# PJ23.net
KiCad netlist of a schematic drawn in EAGLE
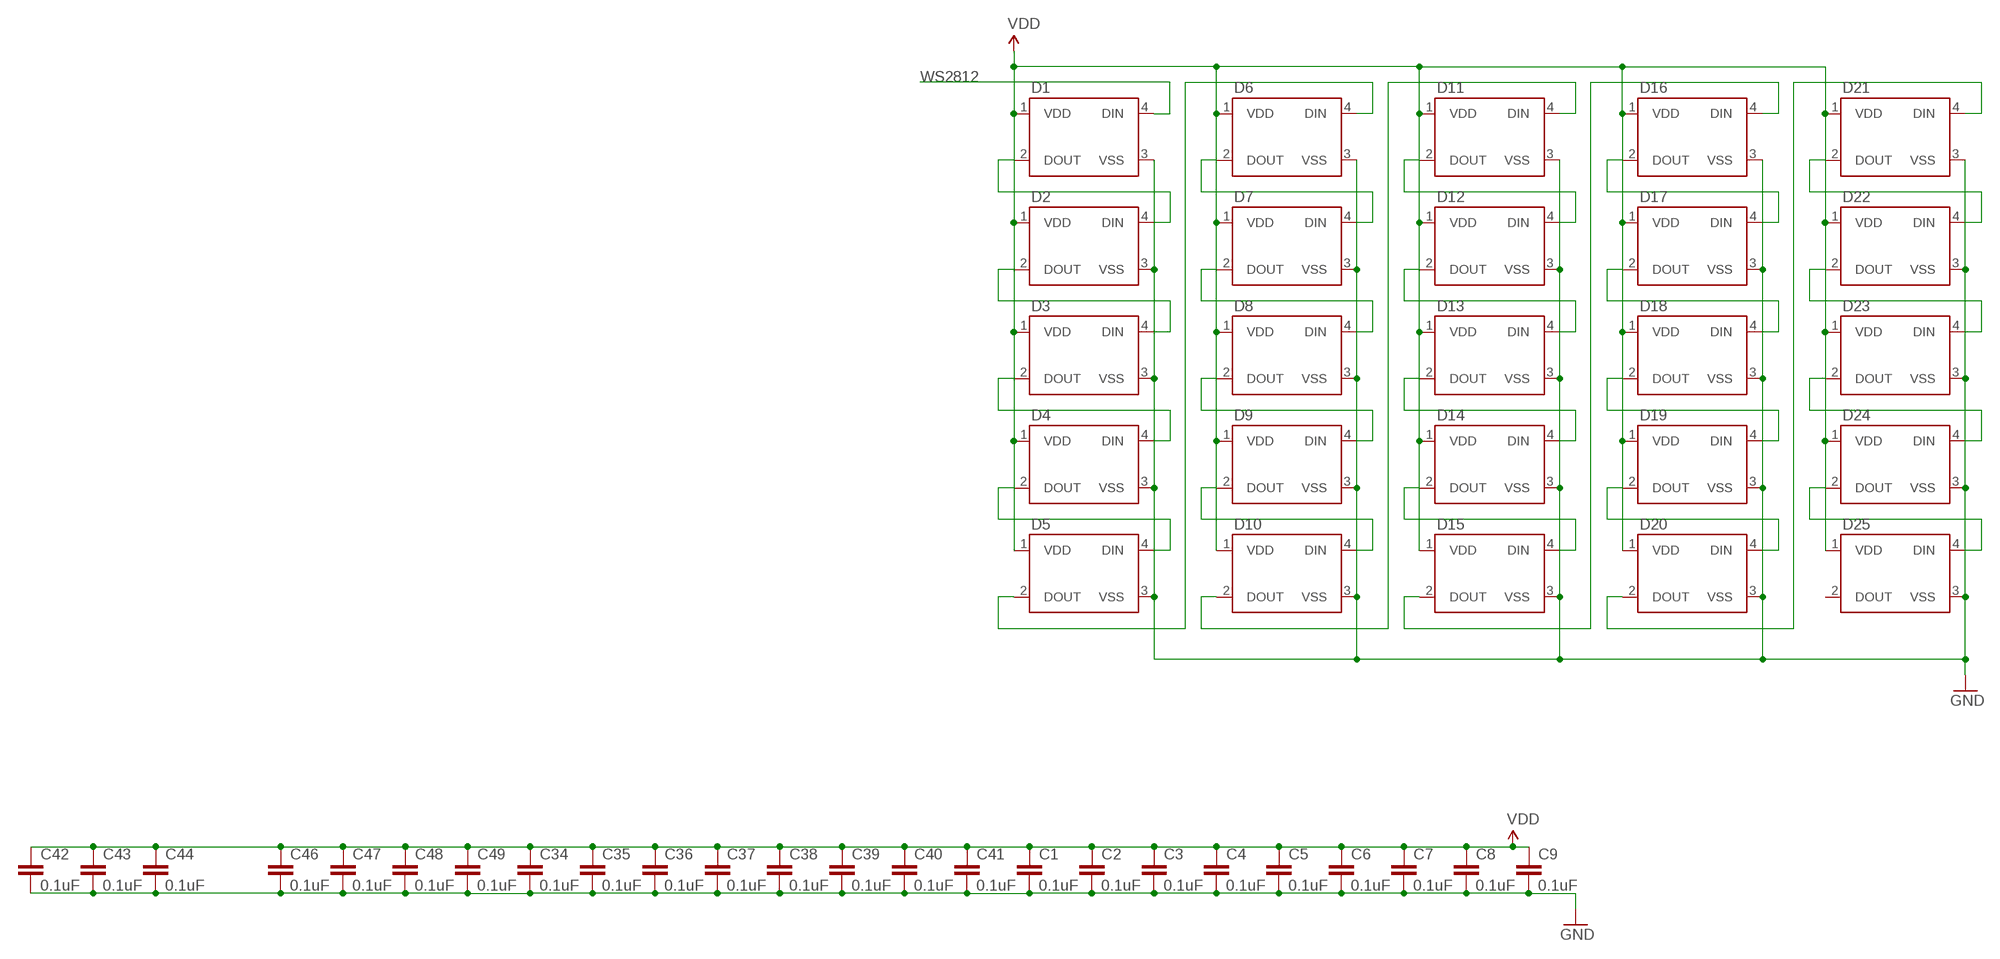
[diagram p0: schematic, sheet 1]
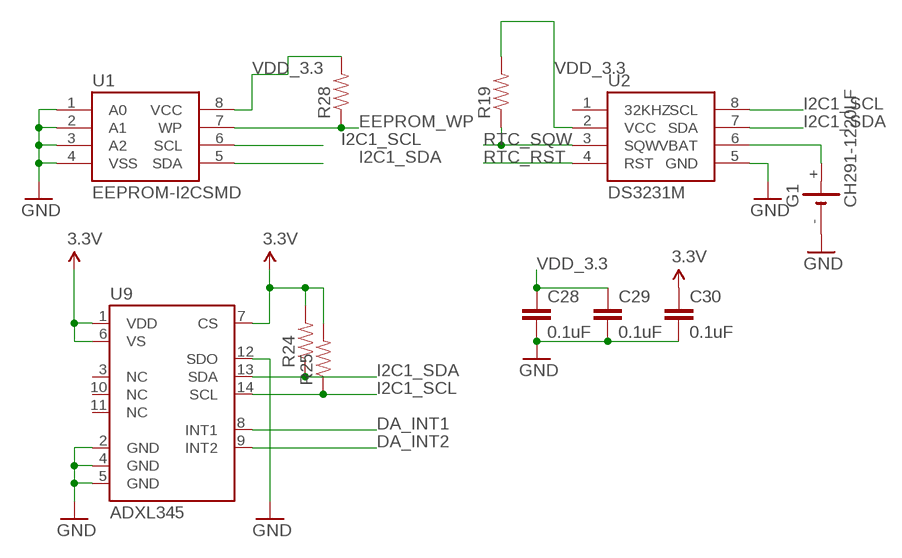
[diagram p1: schematic, sheet 2]
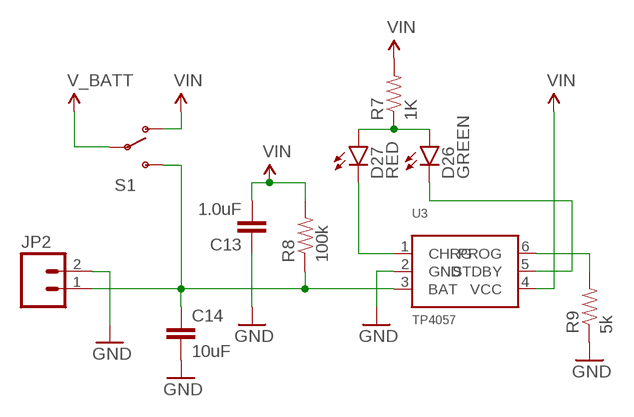
[diagram p2: schematic, sheet 3]
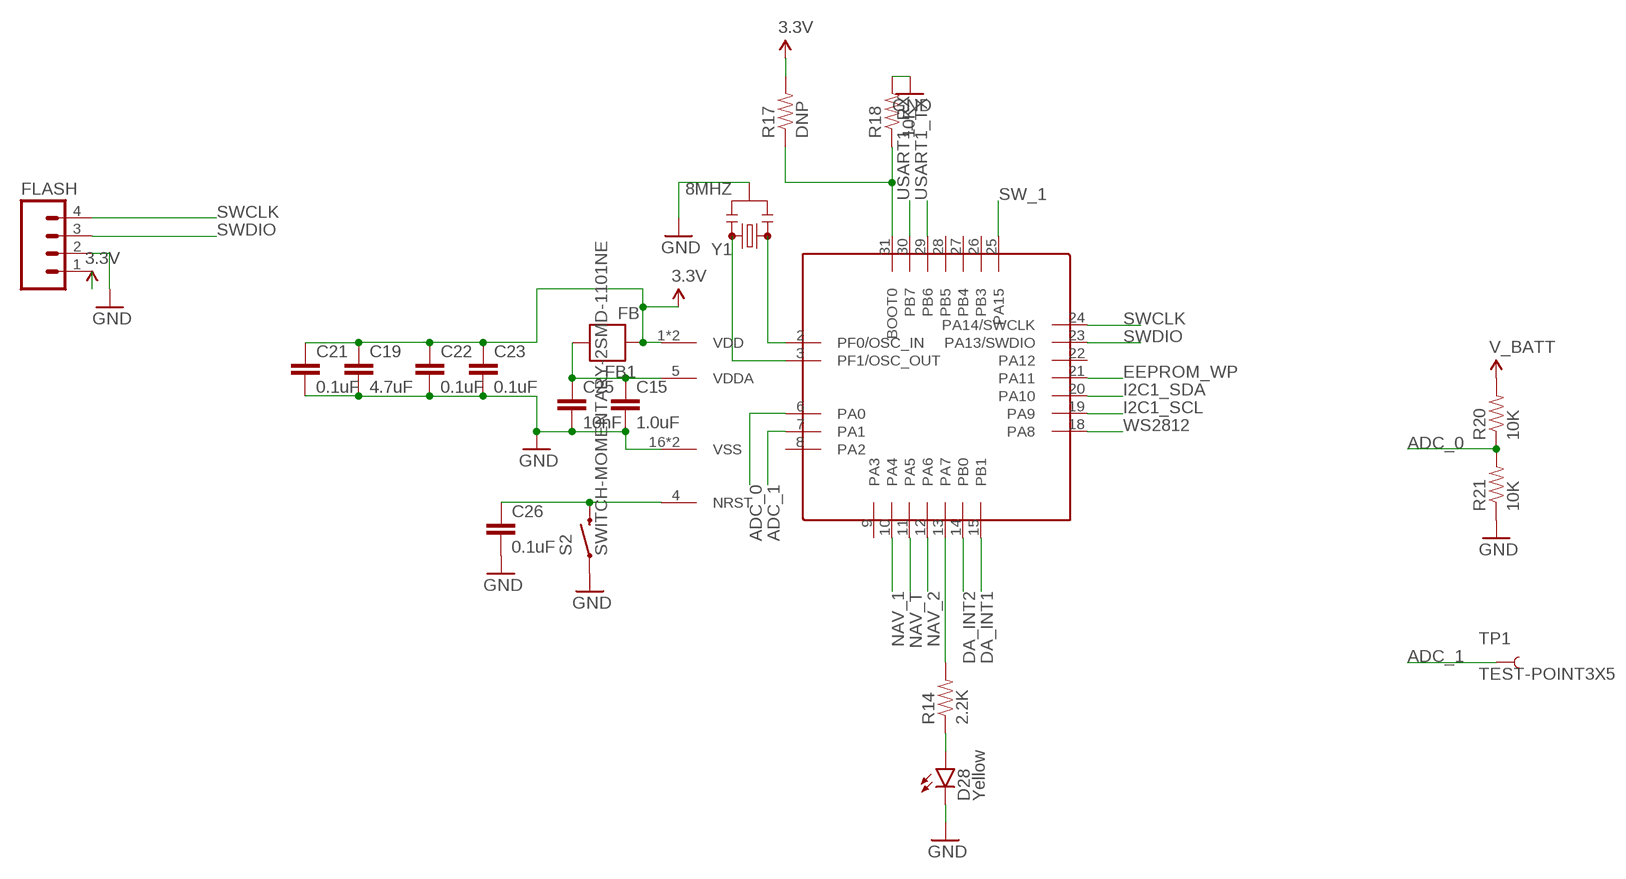
[diagram p3: schematic, sheet 4]
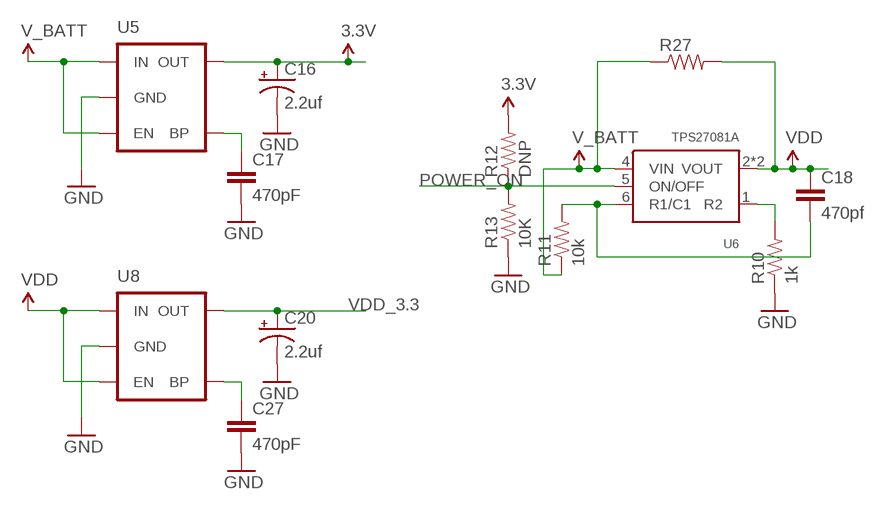
[diagram p4: schematic, sheet 5]
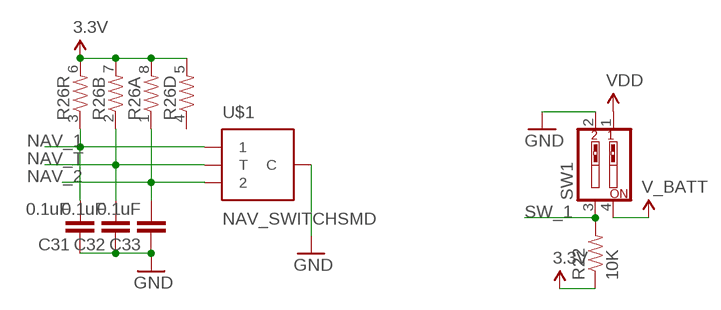
[diagram p5: schematic, sheet 6]
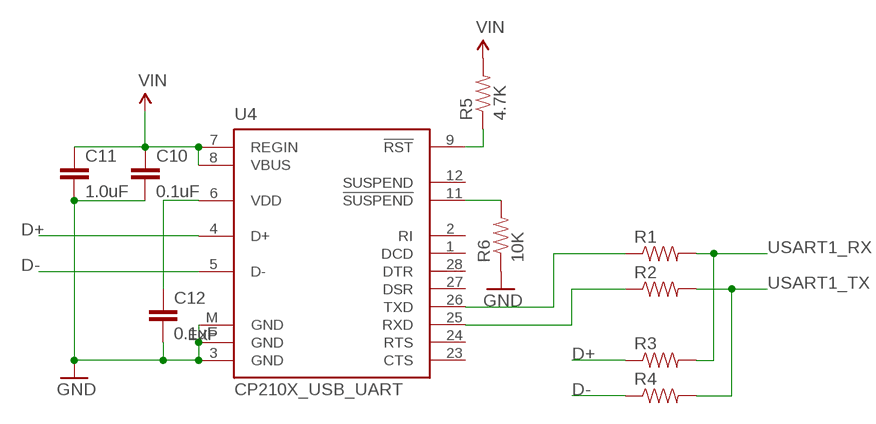
[diagram p6: schematic, sheet 7]
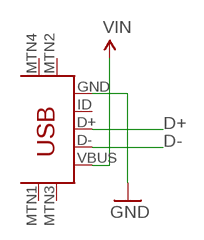
[diagram p7: schematic, sheet 8]

(export (version "E")
  (design (tool "Eeschema 10.0.6"))
  (components
    (comp (ref "JP1")
      (value "USB-MINIB-5PIN")
      (footprint "eagle-import:USB-MINIB")
      (libsource (lib "eagle-import") (part "USB-MINIB-5PIN"))
    )
    (comp (ref "C13")
      (value "1.0uF")
      (footprint "eagle-import:0805-CAP")
      (libsource (lib "eagle-import") (part "1.0UF-25V-+80/-20(0805){dblquote}"))
    )
    (comp (ref "C14")
      (value "10uF")
      (footprint "eagle-import:1206")
      (libsource (lib "eagle-import") (part "10UF-6.3V-20%(1206)"))
    )
    (comp (ref "D26")
      (value "GREEN")
      (footprint "eagle-import:LED-0603")
      (libsource (lib "eagle-import") (part "LED-GREEN0603"))
    )
    (comp (ref "D27")
      (value "RED")
      (footprint "eagle-import:LED-0603")
      (libsource (lib "eagle-import") (part "LED-RED0603"))
    )
    (comp (ref "JP2")
      (value "M02LOCK")
      (footprint "eagle-import:1X02_LOCK")
      (libsource (lib "eagle-import") (part "M02LOCK"))
    )
    (comp (ref "R7")
      (value "1K")
      (footprint "eagle-import:0603-RES")
      (libsource (lib "eagle-import") (part "1KOHM-1/10W-1%(0603)"))
    )
    (comp (ref "R8")
      (value "100k")
      (footprint "eagle-import:0603-RES")
      (libsource (lib "eagle-import") (part "100KOHM-1/10W-1%(0603)"))
    )
    (comp (ref "R9")
      (value "5k")
      (footprint "eagle-import:0805")
      (libsource (lib "eagle-import") (part "RESISTOR0805-RES"))
    )
    (comp (ref "S1")
      (value "SWITCH-SPDT-SMD-A")
      (footprint "eagle-import:SWITCH-SPST-SMD-A")
      (libsource (lib "eagle-import") (part "SWITCH-SPDT-SMD-A"))
    )
    (comp (ref "U3")
      (value "TP4057")
      (footprint "eagle-import:SOT23-6")
      (libsource (lib "eagle-import") (part "TP4057"))
    )
    (comp (ref "C10")
      (value "0.1uF")
      (footprint "eagle-import:0603-CAP")
      (libsource (lib "eagle-import") (part "0.1UF-25V-5%(0603)"))
    )
    (comp (ref "C11")
      (value "1.0uF")
      (footprint "eagle-import:0805-CAP")
      (libsource (lib "eagle-import") (part "1.0UF-25V-+80/-20(0805){dblquote}"))
    )
    (comp (ref "C12")
      (value "0.1uF")
      (footprint "eagle-import:0603-CAP")
      (libsource (lib "eagle-import") (part "0.1UF-25V-5%(0603)"))
    )
    (comp (ref "R1")
      (value "RESISTOR0603")
      (footprint "eagle-import:0603-RES")
      (libsource (lib "eagle-import") (part "RESISTOR0603"))
    )
    (comp (ref "R2")
      (value "RESISTOR0603")
      (footprint "eagle-import:0603-RES")
      (libsource (lib "eagle-import") (part "RESISTOR0603"))
    )
    (comp (ref "R3")
      (value "RESISTOR0603")
      (footprint "eagle-import:0603-RES")
      (libsource (lib "eagle-import") (part "RESISTOR0603"))
    )
    (comp (ref "R4")
      (value "RESISTOR0603")
      (footprint "eagle-import:0603-RES")
      (libsource (lib "eagle-import") (part "RESISTOR0603"))
    )
    (comp (ref "R5")
      (value "4.7K")
      (footprint "eagle-import:0603-RES")
      (libsource (lib "eagle-import") (part "4.7KOHM-1/10W-1%(0603)"))
    )
    (comp (ref "R6")
      (value "10K")
      (footprint "eagle-import:0603-RES")
      (libsource (lib "eagle-import") (part "10KOHM-1/10W-1%(0603)0603"))
    )
    (comp (ref "U4")
      (value "CP210X_USB_UART")
      (footprint "eagle-import:MLP28")
      (libsource (lib "eagle-import") (part "CP210X_USB_UART"))
    )
    (comp (ref "C15")
      (value "1.0uF")
      (footprint "eagle-import:0603-CAP")
      (libsource (lib "eagle-import") (part "1.0UF-16V-10%(0603)"))
    )
    (comp (ref "C19")
      (value "4.7uF")
      (footprint "eagle-import:0603-CAP")
      (libsource (lib "eagle-import") (part "4.7UF-6.3V-10%(0603)0603"))
    )
    (comp (ref "C21")
      (value "0.1uF")
      (footprint "eagle-import:0402-CAP")
      (libsource (lib "eagle-import") (part "CAP0402-CAP"))
    )
    (comp (ref "C22")
      (value "0.1uF")
      (footprint "eagle-import:0402-CAP")
      (libsource (lib "eagle-import") (part "CAP0402-CAP"))
    )
    (comp (ref "C23")
      (value "0.1uF")
      (footprint "eagle-import:0402-CAP")
      (libsource (lib "eagle-import") (part "CAP0402-CAP"))
    )
    (comp (ref "C25")
      (value "10nF")
      (footprint "eagle-import:0402-CAP")
      (libsource (lib "eagle-import") (part "CAP0402-CAP"))
    )
    (comp (ref "C26")
      (value "0.1uF")
      (footprint "eagle-import:0402-CAP")
      (libsource (lib "eagle-import") (part "CAP0402-CAP"))
    )
    (comp (ref "D28")
      (value "Yellow")
      (footprint "eagle-import:LED-0603")
      (libsource (lib "eagle-import") (part "LED-YELLOW0603"))
    )
    (comp (ref "FB1")
      (value "FB")
      (footprint "eagle-import:0603")
      (libsource (lib "eagle-import") (part "FB"))
    )
    (comp (ref "FLASH")
      (value "M04SMD")
      (footprint "eagle-import:1X04-SMD")
      (libsource (lib "eagle-import") (part "M04SMD"))
    )
    (comp (ref "R14")
      (value "2.2K")
      (footprint "eagle-import:0402-RES")
      (libsource (lib "eagle-import") (part "RESISTOR0402"))
    )
    (comp (ref "R17")
      (value "DNP")
      (footprint "eagle-import:0402-RES")
      (libsource (lib "eagle-import") (part "22OHM1/10W1%(0402)"))
    )
    (comp (ref "R18")
      (value "10K")
      (footprint "eagle-import:0402-RES")
      (libsource (lib "eagle-import") (part "22OHM1/10W1%(0402)"))
    )
    (comp (ref "R20")
      (value "10K")
      (footprint "eagle-import:0402-RES")
      (libsource (lib "eagle-import") (part "22OHM1/10W1%(0402)"))
    )
    (comp (ref "R21")
      (value "10K")
      (footprint "eagle-import:0402-RES")
      (libsource (lib "eagle-import") (part "22OHM1/10W1%(0402)"))
    )
    (comp (ref "S2")
      (value "SWITCH-MOMENTARY-2SMD-1101NE")
      (footprint "eagle-import:TACTILE-SWITCH-1101NE")
      (libsource (lib "eagle-import") (part "SWITCH-MOMENTARY-2SMD-1101NE"))
    )
    (comp (ref "TP1")
      (value "TEST-POINT3X5")
      (footprint "eagle-import:PAD.03X.05")
      (libsource (lib "eagle-import") (part "TEST-POINT3X5"))
    )
    (comp (ref "U7")
      (value "STM32F030K6P6")
      (footprint "eagle-import:LQFP32-0.8")
      (libsource (lib "eagle-import") (part "STM32F030K6P6"))
    )
    (comp (ref "Y1")
      (value "8MHZ")
      (footprint "eagle-import:RESONATOR-SMD")
      (libsource (lib "eagle-import") (part "RESONATOR8MHZ"))
    )
    (comp (ref "C16")
      (value "2.2uf")
      (footprint "eagle-import:EIA3216")
      (libsource (lib "eagle-import") (part "10UF-16V-10%(TANT)"))
    )
    (comp (ref "C17")
      (value "470pF")
      (footprint "eagle-import:0805")
      (libsource (lib "eagle-import") (part "SparkFun-Passives_CAP0805"))
    )
    (comp (ref "C18")
      (value "470pf")
      (footprint "eagle-import:1206")
      (libsource (lib "eagle-import") (part "CAP1206"))
    )
    (comp (ref "C20")
      (value "2.2uf")
      (footprint "eagle-import:EIA3216")
      (libsource (lib "eagle-import") (part "10UF-16V-10%(TANT)"))
    )
    (comp (ref "C27")
      (value "470pF")
      (footprint "eagle-import:0805")
      (libsource (lib "eagle-import") (part "SparkFun-Passives_CAP0805"))
    )
    (comp (ref "R10")
      (value "1k")
      (footprint "eagle-import:0805")
      (libsource (lib "eagle-import") (part "RESISTOR0805-RES"))
    )
    (comp (ref "R11")
      (value "10k")
      (footprint "eagle-import:0805")
      (libsource (lib "eagle-import") (part "RESISTOR0805-RES"))
    )
    (comp (ref "R12")
      (value "DNP")
      (footprint "eagle-import:0603-RES")
      (libsource (lib "eagle-import") (part "10KOHM-1/10W-1%(0603)0603"))
    )
    (comp (ref "R13")
      (value "10K")
      (footprint "eagle-import:0603-RES")
      (libsource (lib "eagle-import") (part "10KOHM-1/10W-1%(0603)0603"))
    )
    (comp (ref "R27")
      (value "RESISTOR0805-RES")
      (footprint "eagle-import:0805")
      (libsource (lib "eagle-import") (part "RESISTOR0805-RES"))
    )
    (comp (ref "U5")
      (value "MIC52053.3V")
      (footprint "eagle-import:SOT23-5")
      (libsource (lib "eagle-import") (part "MIC52053.3V"))
    )
    (comp (ref "U6")
      (value "TPS27081A")
      (footprint "eagle-import:DDC(R-PDSO-G6)")
      (libsource (lib "eagle-import") (part "TPS27081A"))
    )
    (comp (ref "U8")
      (value "MIC52053.3V")
      (footprint "eagle-import:SOT23-5")
      (libsource (lib "eagle-import") (part "MIC52053.3V"))
    )
    (comp (ref "C31")
      (value "0.1uF")
      (footprint "eagle-import:0603-CAP")
      (libsource (lib "eagle-import") (part "0.1UF-25V-5%(0603)"))
    )
    (comp (ref "C32")
      (value "0.1uF")
      (footprint "eagle-import:0603-CAP")
      (libsource (lib "eagle-import") (part "0.1UF-25V-5%(0603)"))
    )
    (comp (ref "C33")
      (value "0.1uF")
      (footprint "eagle-import:0603-CAP")
      (libsource (lib "eagle-import") (part "0.1UF-25V-5%(0603)"))
    )
    (comp (ref "R22")
      (value "10K")
      (footprint "eagle-import:0603-RES")
      (libsource (lib "eagle-import") (part "RESISTOR0603"))
    )
    (comp (ref "R26")
      (value "RESISTOR-ARRAY0603-ARV")
      (footprint "eagle-import:0603-ARV")
      (libsource (lib "eagle-import") (part "RESISTOR-ARRAY0603-ARV"))
    )
    (comp (ref "SW1")
      (value "SW_DIP-2-SMT-HALFSIZE")
      (footprint "eagle-import:DIPSWITCH-02-50MIL")
      (libsource (lib "eagle-import") (part "SW_DIP-2-SMT-HALFSIZE"))
    )
    (comp (ref "U$1")
      (value "NAV_SWITCHSMD")
      (footprint "eagle-import:NAV_SWITCH")
      (libsource (lib "eagle-import") (part "NAV_SWITCHSMD"))
    )
    (comp (ref "C28")
      (value "0.1uF")
      (footprint "eagle-import:0603-CAP")
      (libsource (lib "eagle-import") (part "0.1UF-25V-5%(0603)"))
    )
    (comp (ref "C29")
      (value "0.1uF")
      (footprint "eagle-import:0603-CAP")
      (libsource (lib "eagle-import") (part "0.1UF-25V-5%(0603)"))
    )
    (comp (ref "C30")
      (value "0.1uF")
      (footprint "eagle-import:0603-CAP")
      (libsource (lib "eagle-import") (part "0.1UF-25V-5%(0603)"))
    )
    (comp (ref "G1")
      (value "CH291-1220LF")
      (footprint "eagle-import:CH291-1220LF")
      (libsource (lib "eagle-import") (part "CH291-1220LF"))
    )
    (comp (ref "R19")
      (value "RESISTOR0603")
      (footprint "eagle-import:0603-RES")
      (libsource (lib "eagle-import") (part "RESISTOR0603"))
    )
    (comp (ref "R24")
      (value "RESISTOR0603")
      (footprint "eagle-import:0603-RES")
      (libsource (lib "eagle-import") (part "RESISTOR0603"))
    )
    (comp (ref "R25")
      (value "RESISTOR0603")
      (footprint "eagle-import:0603-RES")
      (libsource (lib "eagle-import") (part "RESISTOR0603"))
    )
    (comp (ref "R28")
      (value "RESISTOR0603")
      (footprint "eagle-import:0603-RES")
      (libsource (lib "eagle-import") (part "RESISTOR0603"))
    )
    (comp (ref "U1")
      (value "EEPROM-I2CSMD")
      (footprint "eagle-import:SO08")
      (libsource (lib "eagle-import") (part "EEPROM-I2CSMD"))
    )
    (comp (ref "U2")
      (value "DS3231M")
      (footprint "eagle-import:SOIC8")
      (libsource (lib "eagle-import") (part "DS3231M"))
    )
    (comp (ref "U9")
      (value "ADXL345")
      (footprint "eagle-import:LGA14")
      (libsource (lib "eagle-import") (part "ADXL345"))
    )
    (comp (ref "C1")
      (value "0.1uF")
      (footprint "eagle-import:0603-CAP")
      (libsource (lib "eagle-import") (part "0.1UF-25V-5%(0603)"))
    )
    (comp (ref "C2")
      (value "0.1uF")
      (footprint "eagle-import:0603-CAP")
      (libsource (lib "eagle-import") (part "0.1UF-25V-5%(0603)"))
    )
    (comp (ref "C3")
      (value "0.1uF")
      (footprint "eagle-import:0603-CAP")
      (libsource (lib "eagle-import") (part "0.1UF-25V-5%(0603)"))
    )
    (comp (ref "C4")
      (value "0.1uF")
      (footprint "eagle-import:0603-CAP")
      (libsource (lib "eagle-import") (part "0.1UF-25V-5%(0603)"))
    )
    (comp (ref "C5")
      (value "0.1uF")
      (footprint "eagle-import:0603-CAP")
      (libsource (lib "eagle-import") (part "0.1UF-25V-5%(0603)"))
    )
    (comp (ref "C6")
      (value "0.1uF")
      (footprint "eagle-import:0603-CAP")
      (libsource (lib "eagle-import") (part "0.1UF-25V-5%(0603)"))
    )
    (comp (ref "C7")
      (value "0.1uF")
      (footprint "eagle-import:0603-CAP")
      (libsource (lib "eagle-import") (part "0.1UF-25V-5%(0603)"))
    )
    (comp (ref "C8")
      (value "0.1uF")
      (footprint "eagle-import:0603-CAP")
      (libsource (lib "eagle-import") (part "0.1UF-25V-5%(0603)"))
    )
    (comp (ref "C9")
      (value "0.1uF")
      (footprint "eagle-import:0603-CAP")
      (libsource (lib "eagle-import") (part "0.1UF-25V-5%(0603)"))
    )
    (comp (ref "C34")
      (value "0.1uF")
      (footprint "eagle-import:0603-CAP")
      (libsource (lib "eagle-import") (part "0.1UF-25V-5%(0603)"))
    )
    (comp (ref "C35")
      (value "0.1uF")
      (footprint "eagle-import:0603-CAP")
      (libsource (lib "eagle-import") (part "0.1UF-25V-5%(0603)"))
    )
    (comp (ref "C36")
      (value "0.1uF")
      (footprint "eagle-import:0603-CAP")
      (libsource (lib "eagle-import") (part "0.1UF-25V-5%(0603)"))
    )
    (comp (ref "C37")
      (value "0.1uF")
      (footprint "eagle-import:0603-CAP")
      (libsource (lib "eagle-import") (part "0.1UF-25V-5%(0603)"))
    )
    (comp (ref "C38")
      (value "0.1uF")
      (footprint "eagle-import:0603-CAP")
      (libsource (lib "eagle-import") (part "0.1UF-25V-5%(0603)"))
    )
    (comp (ref "C39")
      (value "0.1uF")
      (footprint "eagle-import:0603-CAP")
      (libsource (lib "eagle-import") (part "0.1UF-25V-5%(0603)"))
    )
    (comp (ref "C40")
      (value "0.1uF")
      (footprint "eagle-import:0603-CAP")
      (libsource (lib "eagle-import") (part "0.1UF-25V-5%(0603)"))
    )
    (comp (ref "C41")
      (value "0.1uF")
      (footprint "eagle-import:0603-CAP")
      (libsource (lib "eagle-import") (part "0.1UF-25V-5%(0603)"))
    )
    (comp (ref "C42")
      (value "0.1uF")
      (footprint "eagle-import:0603-CAP")
      (libsource (lib "eagle-import") (part "0.1UF-25V-5%(0603)"))
    )
    (comp (ref "C43")
      (value "0.1uF")
      (footprint "eagle-import:0603-CAP")
      (libsource (lib "eagle-import") (part "0.1UF-25V-5%(0603)"))
    )
    (comp (ref "C44")
      (value "0.1uF")
      (footprint "eagle-import:0603-CAP")
      (libsource (lib "eagle-import") (part "0.1UF-25V-5%(0603)"))
    )
    (comp (ref "C46")
      (value "0.1uF")
      (footprint "eagle-import:0603-CAP")
      (libsource (lib "eagle-import") (part "0.1UF-25V-5%(0603)"))
    )
    (comp (ref "C47")
      (value "0.1uF")
      (footprint "eagle-import:0603-CAP")
      (libsource (lib "eagle-import") (part "0.1UF-25V-5%(0603)"))
    )
    (comp (ref "C48")
      (value "0.1uF")
      (footprint "eagle-import:0603-CAP")
      (libsource (lib "eagle-import") (part "0.1UF-25V-5%(0603)"))
    )
    (comp (ref "C49")
      (value "0.1uF")
      (footprint "eagle-import:0603-CAP")
      (libsource (lib "eagle-import") (part "0.1UF-25V-5%(0603)"))
    )
    (comp (ref "D1")
      (value "WS2812B")
      (footprint "eagle-import:WS2812B")
      (libsource (lib "eagle-import") (part "WS2812B"))
    )
    (comp (ref "D2")
      (value "WS2812B")
      (footprint "eagle-import:WS2812B")
      (libsource (lib "eagle-import") (part "WS2812B"))
    )
    (comp (ref "D3")
      (value "WS2812B")
      (footprint "eagle-import:WS2812B")
      (libsource (lib "eagle-import") (part "WS2812B"))
    )
    (comp (ref "D4")
      (value "WS2812B")
      (footprint "eagle-import:WS2812B")
      (libsource (lib "eagle-import") (part "WS2812B"))
    )
    (comp (ref "D5")
      (value "WS2812B")
      (footprint "eagle-import:WS2812B")
      (libsource (lib "eagle-import") (part "WS2812B"))
    )
    (comp (ref "D6")
      (value "WS2812B")
      (footprint "eagle-import:WS2812B")
      (libsource (lib "eagle-import") (part "WS2812B"))
    )
    (comp (ref "D7")
      (value "WS2812B")
      (footprint "eagle-import:WS2812B")
      (libsource (lib "eagle-import") (part "WS2812B"))
    )
    (comp (ref "D8")
      (value "WS2812B")
      (footprint "eagle-import:WS2812B")
      (libsource (lib "eagle-import") (part "WS2812B"))
    )
    (comp (ref "D9")
      (value "WS2812B")
      (footprint "eagle-import:WS2812B")
      (libsource (lib "eagle-import") (part "WS2812B"))
    )
    (comp (ref "D10")
      (value "WS2812B")
      (footprint "eagle-import:WS2812B")
      (libsource (lib "eagle-import") (part "WS2812B"))
    )
    (comp (ref "D11")
      (value "WS2812B")
      (footprint "eagle-import:WS2812B")
      (libsource (lib "eagle-import") (part "WS2812B"))
    )
    (comp (ref "D12")
      (value "WS2812B")
      (footprint "eagle-import:WS2812B")
      (libsource (lib "eagle-import") (part "WS2812B"))
    )
    (comp (ref "D13")
      (value "WS2812B")
      (footprint "eagle-import:WS2812B")
      (libsource (lib "eagle-import") (part "WS2812B"))
    )
    (comp (ref "D14")
      (value "WS2812B")
      (footprint "eagle-import:WS2812B")
      (libsource (lib "eagle-import") (part "WS2812B"))
    )
    (comp (ref "D15")
      (value "WS2812B")
      (footprint "eagle-import:WS2812B")
      (libsource (lib "eagle-import") (part "WS2812B"))
    )
    (comp (ref "D16")
      (value "WS2812B")
      (footprint "eagle-import:WS2812B")
      (libsource (lib "eagle-import") (part "WS2812B"))
    )
    (comp (ref "D17")
      (value "WS2812B")
      (footprint "eagle-import:WS2812B")
      (libsource (lib "eagle-import") (part "WS2812B"))
    )
    (comp (ref "D18")
      (value "WS2812B")
      (footprint "eagle-import:WS2812B")
      (libsource (lib "eagle-import") (part "WS2812B"))
    )
    (comp (ref "D19")
      (value "WS2812B")
      (footprint "eagle-import:WS2812B")
      (libsource (lib "eagle-import") (part "WS2812B"))
    )
    (comp (ref "D20")
      (value "WS2812B")
      (footprint "eagle-import:WS2812B")
      (libsource (lib "eagle-import") (part "WS2812B"))
    )
    (comp (ref "D21")
      (value "WS2812B")
      (footprint "eagle-import:WS2812B")
      (libsource (lib "eagle-import") (part "WS2812B"))
    )
    (comp (ref "D22")
      (value "WS2812B")
      (footprint "eagle-import:WS2812B")
      (libsource (lib "eagle-import") (part "WS2812B"))
    )
    (comp (ref "D23")
      (value "WS2812B")
      (footprint "eagle-import:WS2812B")
      (libsource (lib "eagle-import") (part "WS2812B"))
    )
    (comp (ref "D24")
      (value "WS2812B")
      (footprint "eagle-import:WS2812B")
      (libsource (lib "eagle-import") (part "WS2812B"))
    )
    (comp (ref "D25")
      (value "WS2812B")
      (footprint "eagle-import:WS2812B")
      (libsource (lib "eagle-import") (part "WS2812B"))
    )
  )
  (nets
    (net (code "1") (name "3.3V") (class "Default")
      (node (ref "C16") (pin "A") (pinfunction "+_A") (pintype "passive"))
      (node (ref "C19") (pin "1") (pinfunction "1_1") (pintype "passive"))
      (node (ref "C21") (pin "1") (pinfunction "1_1") (pintype "passive"))
      (node (ref "C22") (pin "1") (pinfunction "1_1") (pintype "passive"))
      (node (ref "C23") (pin "1") (pinfunction "1_1") (pintype "passive"))
      (node (ref "C30") (pin "1") (pinfunction "1_1") (pintype "passive"))
      (node (ref "FB1") (pin "2") (pinfunction "P$2_2") (pintype "bidirectional"))
      (node (ref "FLASH") (pin "1") (pinfunction "1_1") (pintype "passive"))
      (node (ref "R12") (pin "2") (pinfunction "2_2") (pintype "passive"))
      (node (ref "R17") (pin "2") (pinfunction "2_2") (pintype "passive"))
      (node (ref "R22") (pin "1") (pinfunction "1_1") (pintype "passive"))
      (node (ref "R24") (pin "2") (pinfunction "2_2") (pintype "passive"))
      (node (ref "R25") (pin "2") (pinfunction "2_2") (pintype "passive"))
      (node (ref "R26") (pin "5") (pinfunction "2_5") (pintype "passive"))
      (node (ref "R26") (pin "6") (pinfunction "2_6") (pintype "passive"))
      (node (ref "R26") (pin "7") (pinfunction "2_7") (pintype "passive"))
      (node (ref "R26") (pin "8") (pinfunction "2_8") (pintype "passive"))
      (node (ref "U5") (pin "5") (pinfunction "OUT_5") (pintype "passive"))
      (node (ref "U7") (pin "1") (pinfunction "VDD_1") (pintype "bidirectional"))
      (node (ref "U7") (pin "17") (pinfunction "VDD_17") (pintype "bidirectional"))
      (node (ref "U9") (pin "1") (pinfunction "VDD_1") (pintype "bidirectional"))
      (node (ref "U9") (pin "6") (pinfunction "VS_6") (pintype "bidirectional"))
      (node (ref "U9") (pin "7") (pinfunction "CS_7") (pintype "bidirectional"))
    )
    (net (code "2") (name "ADC_0") (class "Default")
      (node (ref "R20") (pin "1") (pinfunction "1_1") (pintype "passive"))
      (node (ref "R21") (pin "2") (pinfunction "2_2") (pintype "passive"))
      (node (ref "U7") (pin "6") (pinfunction "PA0_6") (pintype "bidirectional"))
    )
    (net (code "3") (name "ADC_1") (class "Default")
      (node (ref "TP1") (pin "P$1") (pinfunction "1_P$1") (pintype "bidirectional"))
      (node (ref "U7") (pin "7") (pinfunction "PA1_7") (pintype "bidirectional"))
    )
    (net (code "4") (name "D+") (class "Default")
      (node (ref "JP1") (pin "D+") (pinfunction "D+_D+") (pintype "bidirectional"))
      (node (ref "R3") (pin "1") (pinfunction "1_1") (pintype "passive"))
      (node (ref "U4") (pin "4") (pinfunction "D+_4") (pintype "bidirectional"))
    )
    (net (code "5") (name "D-") (class "Default")
      (node (ref "JP1") (pin "D-") (pinfunction "D-_D-") (pintype "bidirectional"))
      (node (ref "R4") (pin "1") (pinfunction "1_1") (pintype "passive"))
      (node (ref "U4") (pin "5") (pinfunction "D-_5") (pintype "bidirectional"))
    )
    (net (code "6") (name "DA_INT1") (class "Default")
      (node (ref "U7") (pin "15") (pinfunction "PB1_15") (pintype "bidirectional"))
      (node (ref "U9") (pin "8") (pinfunction "INT1_8") (pintype "bidirectional"))
    )
    (net (code "7") (name "DA_INT2") (class "Default")
      (node (ref "U7") (pin "14") (pinfunction "PB0_14") (pintype "bidirectional"))
      (node (ref "U9") (pin "9") (pinfunction "INT2_9") (pintype "bidirectional"))
    )
    (net (code "8") (name "EEPROM_WP") (class "Default")
      (node (ref "R28") (pin "1") (pinfunction "1_1") (pintype "passive"))
      (node (ref "U1") (pin "7") (pinfunction "WP_7") (pintype "bidirectional"))
      (node (ref "U7") (pin "21") (pinfunction "PA11_21") (pintype "bidirectional"))
    )
    (net (code "9") (name "GND") (class "Default")
      (node (ref "C1") (pin "2") (pinfunction "2_2") (pintype "passive"))
      (node (ref "C10") (pin "2") (pinfunction "2_2") (pintype "passive"))
      (node (ref "C11") (pin "2") (pinfunction "2_2") (pintype "passive"))
      (node (ref "C12") (pin "2") (pinfunction "2_2") (pintype "passive"))
      (node (ref "C13") (pin "1") (pinfunction "1_1") (pintype "passive"))
      (node (ref "C14") (pin "2") (pinfunction "2_2") (pintype "passive"))
      (node (ref "C15") (pin "2") (pinfunction "2_2") (pintype "passive"))
      (node (ref "C16") (pin "C") (pinfunction "-_C") (pintype "passive"))
      (node (ref "C17") (pin "2") (pinfunction "2_2") (pintype "passive"))
      (node (ref "C19") (pin "2") (pinfunction "2_2") (pintype "passive"))
      (node (ref "C2") (pin "2") (pinfunction "2_2") (pintype "passive"))
      (node (ref "C20") (pin "C") (pinfunction "-_C") (pintype "passive"))
      (node (ref "C21") (pin "2") (pinfunction "2_2") (pintype "passive"))
      (node (ref "C22") (pin "2") (pinfunction "2_2") (pintype "passive"))
      (node (ref "C23") (pin "2") (pinfunction "2_2") (pintype "passive"))
      (node (ref "C25") (pin "2") (pinfunction "2_2") (pintype "passive"))
      (node (ref "C26") (pin "2") (pinfunction "2_2") (pintype "passive"))
      (node (ref "C27") (pin "2") (pinfunction "2_2") (pintype "passive"))
      (node (ref "C28") (pin "2") (pinfunction "2_2") (pintype "passive"))
      (node (ref "C29") (pin "2") (pinfunction "2_2") (pintype "passive"))
      (node (ref "C3") (pin "2") (pinfunction "2_2") (pintype "passive"))
      (node (ref "C30") (pin "2") (pinfunction "2_2") (pintype "passive"))
      (node (ref "C31") (pin "1") (pinfunction "1_1") (pintype "passive"))
      (node (ref "C32") (pin "1") (pinfunction "1_1") (pintype "passive"))
      (node (ref "C33") (pin "1") (pinfunction "1_1") (pintype "passive"))
      (node (ref "C34") (pin "2") (pinfunction "2_2") (pintype "passive"))
      (node (ref "C35") (pin "2") (pinfunction "2_2") (pintype "passive"))
      (node (ref "C36") (pin "2") (pinfunction "2_2") (pintype "passive"))
      (node (ref "C37") (pin "2") (pinfunction "2_2") (pintype "passive"))
      (node (ref "C38") (pin "2") (pinfunction "2_2") (pintype "passive"))
      (node (ref "C39") (pin "2") (pinfunction "2_2") (pintype "passive"))
      (node (ref "C4") (pin "2") (pinfunction "2_2") (pintype "passive"))
      (node (ref "C40") (pin "2") (pinfunction "2_2") (pintype "passive"))
      (node (ref "C41") (pin "2") (pinfunction "2_2") (pintype "passive"))
      (node (ref "C42") (pin "2") (pinfunction "2_2") (pintype "passive"))
      (node (ref "C43") (pin "2") (pinfunction "2_2") (pintype "passive"))
      (node (ref "C44") (pin "2") (pinfunction "2_2") (pintype "passive"))
      (node (ref "C46") (pin "2") (pinfunction "2_2") (pintype "passive"))
      (node (ref "C47") (pin "2") (pinfunction "2_2") (pintype "passive"))
      (node (ref "C48") (pin "2") (pinfunction "2_2") (pintype "passive"))
      (node (ref "C49") (pin "2") (pinfunction "2_2") (pintype "passive"))
      (node (ref "C5") (pin "2") (pinfunction "2_2") (pintype "passive"))
      (node (ref "C6") (pin "2") (pinfunction "2_2") (pintype "passive"))
      (node (ref "C7") (pin "2") (pinfunction "2_2") (pintype "passive"))
      (node (ref "C8") (pin "2") (pinfunction "2_2") (pintype "passive"))
      (node (ref "C9") (pin "2") (pinfunction "2_2") (pintype "passive"))
      (node (ref "D1") (pin "3") (pinfunction "VSS_3") (pintype "power_in"))
      (node (ref "D10") (pin "3") (pinfunction "VSS_3") (pintype "power_in"))
      (node (ref "D11") (pin "3") (pinfunction "VSS_3") (pintype "power_in"))
      (node (ref "D12") (pin "3") (pinfunction "VSS_3") (pintype "power_in"))
      (node (ref "D13") (pin "3") (pinfunction "VSS_3") (pintype "power_in"))
      (node (ref "D14") (pin "3") (pinfunction "VSS_3") (pintype "power_in"))
      (node (ref "D15") (pin "3") (pinfunction "VSS_3") (pintype "power_in"))
      (node (ref "D16") (pin "3") (pinfunction "VSS_3") (pintype "power_in"))
      (node (ref "D17") (pin "3") (pinfunction "VSS_3") (pintype "power_in"))
      (node (ref "D18") (pin "3") (pinfunction "VSS_3") (pintype "power_in"))
      (node (ref "D19") (pin "3") (pinfunction "VSS_3") (pintype "power_in"))
      (node (ref "D2") (pin "3") (pinfunction "VSS_3") (pintype "power_in"))
      (node (ref "D20") (pin "3") (pinfunction "VSS_3") (pintype "power_in"))
      (node (ref "D21") (pin "3") (pinfunction "VSS_3") (pintype "power_in"))
      (node (ref "D22") (pin "3") (pinfunction "VSS_3") (pintype "power_in"))
      (node (ref "D23") (pin "3") (pinfunction "VSS_3") (pintype "power_in"))
      (node (ref "D24") (pin "3") (pinfunction "VSS_3") (pintype "power_in"))
      (node (ref "D25") (pin "3") (pinfunction "VSS_3") (pintype "power_in"))
      (node (ref "D28") (pin "C") (pinfunction "C_C") (pintype "passive"))
      (node (ref "D3") (pin "3") (pinfunction "VSS_3") (pintype "power_in"))
      (node (ref "D4") (pin "3") (pinfunction "VSS_3") (pintype "power_in"))
      (node (ref "D5") (pin "3") (pinfunction "VSS_3") (pintype "power_in"))
      (node (ref "D6") (pin "3") (pinfunction "VSS_3") (pintype "power_in"))
      (node (ref "D7") (pin "3") (pinfunction "VSS_3") (pintype "power_in"))
      (node (ref "D8") (pin "3") (pinfunction "VSS_3") (pintype "power_in"))
      (node (ref "D9") (pin "3") (pinfunction "VSS_3") (pintype "power_in"))
      (node (ref "FLASH") (pin "2") (pinfunction "2_2") (pintype "passive"))
      (node (ref "G1") (pin "-") (pinfunction "-_-") (pintype "passive"))
      (node (ref "JP1") (pin "GND") (pinfunction "GND_GND") (pintype "bidirectional"))
      (node (ref "JP2") (pin "2") (pinfunction "2_2") (pintype "passive"))
      (node (ref "R10") (pin "1") (pinfunction "1_1") (pintype "passive"))
      (node (ref "R13") (pin "1") (pinfunction "1_1") (pintype "passive"))
      (node (ref "R18") (pin "2") (pinfunction "2_2") (pintype "passive"))
      (node (ref "R21") (pin "1") (pinfunction "1_1") (pintype "passive"))
      (node (ref "R6") (pin "1") (pinfunction "1_1") (pintype "passive"))
      (node (ref "R9") (pin "1") (pinfunction "1_1") (pintype "passive"))
      (node (ref "S2") (pin "1") (pinfunction "1_1") (pintype "passive"))
      (node (ref "SW1") (pin "2") (pinfunction "2_2") (pintype "passive"))
      (node (ref "U$1") (pin "C") (pinfunction "C_C") (pintype "power_in"))
      (node (ref "U1") (pin "1") (pinfunction "A0_1") (pintype "bidirectional"))
      (node (ref "U1") (pin "2") (pinfunction "A1_2") (pintype "bidirectional"))
      (node (ref "U1") (pin "3") (pinfunction "A2_3") (pintype "bidirectional"))
      (node (ref "U1") (pin "4") (pinfunction "VSS_4") (pintype "power_in"))
      (node (ref "U2") (pin "5") (pinfunction "GND_5") (pintype "power_in"))
      (node (ref "U3") (pin "2") (pinfunction "GND_2") (pintype "bidirectional"))
      (node (ref "U4") (pin "3") (pinfunction "GND_3") (pintype "power_in"))
      (node (ref "U4") (pin "EXP") (pinfunction "GND_EXP") (pintype "power_in"))
      (node (ref "U4") (pin "M") (pinfunction "GND_M") (pintype "power_in"))
      (node (ref "U5") (pin "2") (pinfunction "GND_2") (pintype "input"))
      (node (ref "U7") (pin "16") (pinfunction "VSS_16") (pintype "bidirectional"))
      (node (ref "U7") (pin "32") (pinfunction "VSS_32") (pintype "bidirectional"))
      (node (ref "U8") (pin "2") (pinfunction "GND_2") (pintype "input"))
      (node (ref "U9") (pin "12") (pinfunction "SDO_12") (pintype "bidirectional"))
      (node (ref "U9") (pin "2") (pinfunction "GND_2") (pintype "bidirectional"))
      (node (ref "U9") (pin "4") (pinfunction "GND_4") (pintype "bidirectional"))
      (node (ref "U9") (pin "5") (pinfunction "GND_5") (pintype "bidirectional"))
      (node (ref "Y1") (pin "2") (pinfunction "2_2") (pintype "passive"))
    )
    (net (code "10") (name "I2C1_SCL") (class "Default")
      (node (ref "R25") (pin "1") (pinfunction "1_1") (pintype "passive"))
      (node (ref "U1") (pin "6") (pinfunction "SCL_6") (pintype "bidirectional"))
      (node (ref "U2") (pin "8") (pinfunction "SCL_8") (pintype "bidirectional"))
      (node (ref "U7") (pin "19") (pinfunction "PA9_19") (pintype "bidirectional"))
      (node (ref "U9") (pin "14") (pinfunction "SCL_14") (pintype "bidirectional"))
    )
    (net (code "11") (name "I2C1_SDA") (class "Default")
      (node (ref "R24") (pin "1") (pinfunction "1_1") (pintype "passive"))
      (node (ref "U1") (pin "5") (pinfunction "SDA_5") (pintype "bidirectional"))
      (node (ref "U2") (pin "7") (pinfunction "SDA_7") (pintype "bidirectional"))
      (node (ref "U7") (pin "20") (pinfunction "PA10_20") (pintype "bidirectional"))
      (node (ref "U9") (pin "13") (pinfunction "SDA_13") (pintype "bidirectional"))
    )
    (net (code "12") (name "NAV_1") (class "Default")
      (node (ref "C31") (pin "2") (pinfunction "2_2") (pintype "passive"))
      (node (ref "R26") (pin "3") (pinfunction "1_3") (pintype "passive"))
      (node (ref "U$1") (pin "1") (pinfunction "1_1") (pintype "input"))
      (node (ref "U7") (pin "10") (pinfunction "PA4_10") (pintype "bidirectional"))
    )
    (net (code "13") (name "NAV_2") (class "Default")
      (node (ref "C33") (pin "2") (pinfunction "2_2") (pintype "passive"))
      (node (ref "R26") (pin "1") (pinfunction "1_1") (pintype "passive"))
      (node (ref "U$1") (pin "2") (pinfunction "2_2") (pintype "input"))
      (node (ref "U7") (pin "12") (pinfunction "PA6_12") (pintype "bidirectional"))
    )
    (net (code "14") (name "NAV_T") (class "Default")
      (node (ref "C32") (pin "2") (pinfunction "2_2") (pintype "passive"))
      (node (ref "R26") (pin "2") (pinfunction "1_2") (pintype "passive"))
      (node (ref "U$1") (pin "T") (pinfunction "T_T") (pintype "input"))
      (node (ref "U7") (pin "11") (pinfunction "PA5_11") (pintype "bidirectional"))
    )
    (net (code "15") (name "Net-(D1-DOUT)") (class "Default")
      (node (ref "D1") (pin "2") (pinfunction "DOUT_2") (pintype "output"))
      (node (ref "D2") (pin "4") (pinfunction "DIN_4") (pintype "input"))
    )
    (net (code "16") (name "Net-(D2-DOUT)") (class "Default")
      (node (ref "D2") (pin "2") (pinfunction "DOUT_2") (pintype "output"))
      (node (ref "D3") (pin "4") (pinfunction "DIN_4") (pintype "input"))
    )
    (net (code "17") (name "Net-(D3-DOUT)") (class "Default")
      (node (ref "D3") (pin "2") (pinfunction "DOUT_2") (pintype "output"))
      (node (ref "D4") (pin "4") (pinfunction "DIN_4") (pintype "input"))
    )
    (net (code "18") (name "Net-(D4-DOUT)") (class "Default")
      (node (ref "D4") (pin "2") (pinfunction "DOUT_2") (pintype "output"))
      (node (ref "D5") (pin "4") (pinfunction "DIN_4") (pintype "input"))
    )
    (net (code "19") (name "Net-(D5-DOUT)") (class "Default")
      (node (ref "D5") (pin "2") (pinfunction "DOUT_2") (pintype "output"))
      (node (ref "D6") (pin "4") (pinfunction "DIN_4") (pintype "input"))
    )
    (net (code "20") (name "Net-(D6-DOUT)") (class "Default")
      (node (ref "D6") (pin "2") (pinfunction "DOUT_2") (pintype "output"))
      (node (ref "D7") (pin "4") (pinfunction "DIN_4") (pintype "input"))
    )
    (net (code "21") (name "Net-(D7-DOUT)") (class "Default")
      (node (ref "D7") (pin "2") (pinfunction "DOUT_2") (pintype "output"))
      (node (ref "D8") (pin "4") (pinfunction "DIN_4") (pintype "input"))
    )
    (net (code "22") (name "Net-(D8-DOUT)") (class "Default")
      (node (ref "D8") (pin "2") (pinfunction "DOUT_2") (pintype "output"))
      (node (ref "D9") (pin "4") (pinfunction "DIN_4") (pintype "input"))
    )
    (net (code "23") (name "Net-(D10-DIN)") (class "Default")
      (node (ref "D10") (pin "4") (pinfunction "DIN_4") (pintype "input"))
      (node (ref "D9") (pin "2") (pinfunction "DOUT_2") (pintype "output"))
    )
    (net (code "24") (name "Net-(D10-DOUT)") (class "Default")
      (node (ref "D10") (pin "2") (pinfunction "DOUT_2") (pintype "output"))
      (node (ref "D11") (pin "4") (pinfunction "DIN_4") (pintype "input"))
    )
    (net (code "25") (name "Net-(D11-DOUT)") (class "Default")
      (node (ref "D11") (pin "2") (pinfunction "DOUT_2") (pintype "output"))
      (node (ref "D12") (pin "4") (pinfunction "DIN_4") (pintype "input"))
    )
    (net (code "26") (name "Net-(D12-DOUT)") (class "Default")
      (node (ref "D12") (pin "2") (pinfunction "DOUT_2") (pintype "output"))
      (node (ref "D13") (pin "4") (pinfunction "DIN_4") (pintype "input"))
    )
    (net (code "27") (name "Net-(D13-DOUT)") (class "Default")
      (node (ref "D13") (pin "2") (pinfunction "DOUT_2") (pintype "output"))
      (node (ref "D14") (pin "4") (pinfunction "DIN_4") (pintype "input"))
    )
    (net (code "28") (name "Net-(D14-DOUT)") (class "Default")
      (node (ref "D14") (pin "2") (pinfunction "DOUT_2") (pintype "output"))
      (node (ref "D15") (pin "4") (pinfunction "DIN_4") (pintype "input"))
    )
    (net (code "29") (name "Net-(D15-DOUT)") (class "Default")
      (node (ref "D15") (pin "2") (pinfunction "DOUT_2") (pintype "output"))
      (node (ref "D16") (pin "4") (pinfunction "DIN_4") (pintype "input"))
    )
    (net (code "30") (name "Net-(D16-DOUT)") (class "Default")
      (node (ref "D16") (pin "2") (pinfunction "DOUT_2") (pintype "output"))
      (node (ref "D17") (pin "4") (pinfunction "DIN_4") (pintype "input"))
    )
    (net (code "31") (name "Net-(D17-DOUT)") (class "Default")
      (node (ref "D17") (pin "2") (pinfunction "DOUT_2") (pintype "output"))
      (node (ref "D18") (pin "4") (pinfunction "DIN_4") (pintype "input"))
    )
    (net (code "32") (name "Net-(D18-DOUT)") (class "Default")
      (node (ref "D18") (pin "2") (pinfunction "DOUT_2") (pintype "output"))
      (node (ref "D19") (pin "4") (pinfunction "DIN_4") (pintype "input"))
    )
    (net (code "33") (name "Net-(D19-DOUT)") (class "Default")
      (node (ref "D19") (pin "2") (pinfunction "DOUT_2") (pintype "output"))
      (node (ref "D20") (pin "4") (pinfunction "DIN_4") (pintype "input"))
    )
    (net (code "34") (name "Net-(D20-DOUT)") (class "Default")
      (node (ref "D20") (pin "2") (pinfunction "DOUT_2") (pintype "output"))
      (node (ref "D21") (pin "4") (pinfunction "DIN_4") (pintype "input"))
    )
    (net (code "35") (name "Net-(D21-DOUT)") (class "Default")
      (node (ref "D21") (pin "2") (pinfunction "DOUT_2") (pintype "output"))
      (node (ref "D22") (pin "4") (pinfunction "DIN_4") (pintype "input"))
    )
    (net (code "36") (name "Net-(D22-DOUT)") (class "Default")
      (node (ref "D22") (pin "2") (pinfunction "DOUT_2") (pintype "output"))
      (node (ref "D23") (pin "4") (pinfunction "DIN_4") (pintype "input"))
    )
    (net (code "37") (name "Net-(D23-DOUT)") (class "Default")
      (node (ref "D23") (pin "2") (pinfunction "DOUT_2") (pintype "output"))
      (node (ref "D24") (pin "4") (pinfunction "DIN_4") (pintype "input"))
    )
    (net (code "38") (name "Net-(D24-DOUT)") (class "Default")
      (node (ref "D24") (pin "2") (pinfunction "DOUT_2") (pintype "output"))
      (node (ref "D25") (pin "4") (pinfunction "DIN_4") (pintype "input"))
    )
    (net (code "39") (name "Net-(D26-PadA)") (class "Default")
      (node (ref "D26") (pin "A") (pinfunction "A_A") (pintype "passive"))
      (node (ref "D27") (pin "A") (pinfunction "A_A") (pintype "passive"))
      (node (ref "R7") (pin "1") (pinfunction "1_1") (pintype "passive"))
    )
    (net (code "40") (name "Net-(D28-PadA)") (class "Default")
      (node (ref "D28") (pin "A") (pinfunction "A_A") (pintype "passive"))
      (node (ref "R14") (pin "1") (pinfunction "1_1") (pintype "passive"))
    )
    (net (code "41") (name "Net-(FB1-P$1)") (class "Default")
      (node (ref "C15") (pin "1") (pinfunction "1_1") (pintype "passive"))
      (node (ref "C25") (pin "1") (pinfunction "1_1") (pintype "passive"))
      (node (ref "FB1") (pin "1") (pinfunction "P$1_1") (pintype "bidirectional"))
      (node (ref "U7") (pin "5") (pinfunction "VDDA_5") (pintype "bidirectional"))
    )
    (net (code "42") (name "Net-(S1-S)") (class "Default")
      (node (ref "C14") (pin "1") (pinfunction "1_1") (pintype "passive"))
      (node (ref "JP2") (pin "1") (pinfunction "1_1") (pintype "passive"))
      (node (ref "R8") (pin "1") (pinfunction "1_1") (pintype "passive"))
      (node (ref "S1") (pin "3") (pinfunction "S_3") (pintype "passive"))
      (node (ref "U3") (pin "3") (pinfunction "BAT_3") (pintype "bidirectional"))
    )
    (net (code "43") (name "Net-(U2-VBAT)") (class "Default")
      (node (ref "G1") (pin "+") (pinfunction "+_+") (pintype "passive"))
      (node (ref "U2") (pin "6") (pinfunction "VBAT_6") (pintype "power_in"))
    )
    (net (code "44") (name "Net-(U3-CHRG)") (class "Default")
      (node (ref "D27") (pin "C") (pinfunction "C_C") (pintype "passive"))
      (node (ref "U3") (pin "1") (pinfunction "CHRG_1") (pintype "bidirectional"))
    )
    (net (code "45") (name "Net-(U3-PROG)") (class "Default")
      (node (ref "R9") (pin "2") (pinfunction "2_2") (pintype "passive"))
      (node (ref "U3") (pin "6") (pinfunction "PROG_6") (pintype "bidirectional"))
    )
    (net (code "46") (name "Net-(U3-STDBY)") (class "Default")
      (node (ref "D26") (pin "C") (pinfunction "C_C") (pintype "passive"))
      (node (ref "U3") (pin "5") (pinfunction "STDBY_5") (pintype "bidirectional"))
    )
    (net (code "47") (name "Net-(U4-RXD)") (class "Default")
      (node (ref "R2") (pin "1") (pinfunction "1_1") (pintype "passive"))
      (node (ref "U4") (pin "25") (pinfunction "RXD_25") (pintype "input"))
    )
    (net (code "48") (name "Net-(U4-TXD)") (class "Default")
      (node (ref "R1") (pin "1") (pinfunction "1_1") (pintype "passive"))
      (node (ref "U4") (pin "26") (pinfunction "TXD_26") (pintype "output"))
    )
    (net (code "49") (name "Net-(U4-VDD)") (class "Default")
      (node (ref "C12") (pin "1") (pinfunction "1_1") (pintype "passive"))
      (node (ref "U4") (pin "6") (pinfunction "VDD_6") (pintype "power_in"))
    )
    (net (code "50") (name "Net-(U4-~{RST})") (class "Default")
      (node (ref "R5") (pin "1") (pinfunction "1_1") (pintype "passive"))
      (node (ref "U4") (pin "9") (pinfunction "~{RST}_9") (pintype "bidirectional"))
    )
    (net (code "51") (name "Net-(U4-~{SUSPEND})") (class "Default")
      (node (ref "R6") (pin "2") (pinfunction "2_2") (pintype "passive"))
      (node (ref "U4") (pin "11") (pinfunction "~{SUSPEND}_11") (pintype "output"))
    )
    (net (code "52") (name "Net-(U5-BP)") (class "Default")
      (node (ref "C17") (pin "1") (pinfunction "1_1") (pintype "passive"))
      (node (ref "U5") (pin "4") (pinfunction "BP_4") (pintype "input"))
    )
    (net (code "53") (name "Net-(U6-R1{slash}C1)") (class "Default")
      (node (ref "C18") (pin "2") (pinfunction "2_2") (pintype "passive"))
      (node (ref "R11") (pin "2") (pinfunction "2_2") (pintype "passive"))
      (node (ref "U6") (pin "6") (pinfunction "R1/C1_6") (pintype "bidirectional"))
    )
    (net (code "54") (name "Net-(U6-R2)") (class "Default")
      (node (ref "R10") (pin "2") (pinfunction "2_2") (pintype "passive"))
      (node (ref "U6") (pin "1") (pinfunction "R2_1") (pintype "bidirectional"))
    )
    (net (code "55") (name "Net-(U7-BOOT0)") (class "Default")
      (node (ref "R17") (pin "1") (pinfunction "1_1") (pintype "passive"))
      (node (ref "R18") (pin "1") (pinfunction "1_1") (pintype "passive"))
      (node (ref "U7") (pin "31") (pinfunction "BOOT0_31") (pintype "bidirectional"))
    )
    (net (code "56") (name "Net-(U7-NRST)") (class "Default")
      (node (ref "C26") (pin "1") (pinfunction "1_1") (pintype "passive"))
      (node (ref "S2") (pin "2") (pinfunction "2_2") (pintype "passive"))
      (node (ref "U7") (pin "4") (pinfunction "NRST_4") (pintype "bidirectional"))
    )
    (net (code "57") (name "Net-(U7-PA7)") (class "Default")
      (node (ref "R14") (pin "2") (pinfunction "2_2") (pintype "passive"))
      (node (ref "U7") (pin "13") (pinfunction "PA7_13") (pintype "bidirectional"))
    )
    (net (code "58") (name "Net-(U7-PF0{slash}OSC_IN)") (class "Default")
      (node (ref "U7") (pin "2") (pinfunction "PF0/OSC_IN_2") (pintype "bidirectional"))
      (node (ref "Y1") (pin "1") (pinfunction "1_1") (pintype "passive"))
    )
    (net (code "59") (name "Net-(U7-PF1{slash}OSC_OUT)") (class "Default")
      (node (ref "U7") (pin "3") (pinfunction "PF1/OSC_OUT_3") (pintype "bidirectional"))
      (node (ref "Y1") (pin "3") (pinfunction "3_3") (pintype "passive"))
    )
    (net (code "60") (name "Net-(U8-BP)") (class "Default")
      (node (ref "C27") (pin "1") (pinfunction "1_1") (pintype "passive"))
      (node (ref "U8") (pin "4") (pinfunction "BP_4") (pintype "input"))
    )
    (net (code "61") (name "POWER_ON") (class "Default")
      (node (ref "R12") (pin "1") (pinfunction "1_1") (pintype "passive"))
      (node (ref "R13") (pin "2") (pinfunction "2_2") (pintype "passive"))
      (node (ref "U6") (pin "5") (pinfunction "ON/OFF_5") (pintype "bidirectional"))
    )
    (net (code "62") (name "RTC_RST") (class "Default")
      (node (ref "U2") (pin "4") (pinfunction "RST_4") (pintype "bidirectional"))
    )
    (net (code "63") (name "RTC_SQW") (class "Default")
      (node (ref "R19") (pin "1") (pinfunction "1_1") (pintype "passive"))
      (node (ref "U2") (pin "3") (pinfunction "SQW_3") (pintype "output"))
    )
    (net (code "64") (name "SWCLK") (class "Default")
      (node (ref "FLASH") (pin "4") (pinfunction "4_4") (pintype "passive"))
      (node (ref "U7") (pin "24") (pinfunction "PA14/SWCLK_24") (pintype "bidirectional"))
    )
    (net (code "65") (name "SWDIO") (class "Default")
      (node (ref "FLASH") (pin "3") (pinfunction "3_3") (pintype "passive"))
      (node (ref "U7") (pin "23") (pinfunction "PA13/SWDIO_23") (pintype "bidirectional"))
    )
    (net (code "66") (name "SW_1") (class "Default")
      (node (ref "R22") (pin "2") (pinfunction "2_2") (pintype "passive"))
      (node (ref "SW1") (pin "3") (pinfunction "3_3") (pintype "passive"))
      (node (ref "U7") (pin "25") (pinfunction "PA15_25") (pintype "bidirectional"))
    )
    (net (code "67") (name "USART1_RX") (class "Default")
      (node (ref "R1") (pin "2") (pinfunction "2_2") (pintype "passive"))
      (node (ref "R3") (pin "2") (pinfunction "2_2") (pintype "passive"))
      (node (ref "U7") (pin "30") (pinfunction "PB7_30") (pintype "bidirectional"))
    )
    (net (code "68") (name "USART1_TX") (class "Default")
      (node (ref "R2") (pin "2") (pinfunction "2_2") (pintype "passive"))
      (node (ref "R4") (pin "2") (pinfunction "2_2") (pintype "passive"))
      (node (ref "U7") (pin "29") (pinfunction "PB6_29") (pintype "bidirectional"))
    )
    (net (code "69") (name "VDD") (class "Default")
      (node (ref "C1") (pin "1") (pinfunction "1_1") (pintype "passive"))
      (node (ref "C18") (pin "1") (pinfunction "1_1") (pintype "passive"))
      (node (ref "C2") (pin "1") (pinfunction "1_1") (pintype "passive"))
      (node (ref "C3") (pin "1") (pinfunction "1_1") (pintype "passive"))
      (node (ref "C34") (pin "1") (pinfunction "1_1") (pintype "passive"))
      (node (ref "C35") (pin "1") (pinfunction "1_1") (pintype "passive"))
      (node (ref "C36") (pin "1") (pinfunction "1_1") (pintype "passive"))
      (node (ref "C37") (pin "1") (pinfunction "1_1") (pintype "passive"))
      (node (ref "C38") (pin "1") (pinfunction "1_1") (pintype "passive"))
      (node (ref "C39") (pin "1") (pinfunction "1_1") (pintype "passive"))
      (node (ref "C4") (pin "1") (pinfunction "1_1") (pintype "passive"))
      (node (ref "C40") (pin "1") (pinfunction "1_1") (pintype "passive"))
      (node (ref "C41") (pin "1") (pinfunction "1_1") (pintype "passive"))
      (node (ref "C42") (pin "1") (pinfunction "1_1") (pintype "passive"))
      (node (ref "C43") (pin "1") (pinfunction "1_1") (pintype "passive"))
      (node (ref "C44") (pin "1") (pinfunction "1_1") (pintype "passive"))
      (node (ref "C46") (pin "1") (pinfunction "1_1") (pintype "passive"))
      (node (ref "C47") (pin "1") (pinfunction "1_1") (pintype "passive"))
      (node (ref "C48") (pin "1") (pinfunction "1_1") (pintype "passive"))
      (node (ref "C49") (pin "1") (pinfunction "1_1") (pintype "passive"))
      (node (ref "C5") (pin "1") (pinfunction "1_1") (pintype "passive"))
      (node (ref "C6") (pin "1") (pinfunction "1_1") (pintype "passive"))
      (node (ref "C7") (pin "1") (pinfunction "1_1") (pintype "passive"))
      (node (ref "C8") (pin "1") (pinfunction "1_1") (pintype "passive"))
      (node (ref "C9") (pin "1") (pinfunction "1_1") (pintype "passive"))
      (node (ref "D1") (pin "1") (pinfunction "VDD_1") (pintype "power_in"))
      (node (ref "D10") (pin "1") (pinfunction "VDD_1") (pintype "power_in"))
      (node (ref "D11") (pin "1") (pinfunction "VDD_1") (pintype "power_in"))
      (node (ref "D12") (pin "1") (pinfunction "VDD_1") (pintype "power_in"))
      (node (ref "D13") (pin "1") (pinfunction "VDD_1") (pintype "power_in"))
      (node (ref "D14") (pin "1") (pinfunction "VDD_1") (pintype "power_in"))
      (node (ref "D15") (pin "1") (pinfunction "VDD_1") (pintype "power_in"))
      (node (ref "D16") (pin "1") (pinfunction "VDD_1") (pintype "power_in"))
      (node (ref "D17") (pin "1") (pinfunction "VDD_1") (pintype "power_in"))
      (node (ref "D18") (pin "1") (pinfunction "VDD_1") (pintype "power_in"))
      (node (ref "D19") (pin "1") (pinfunction "VDD_1") (pintype "power_in"))
      (node (ref "D2") (pin "1") (pinfunction "VDD_1") (pintype "power_in"))
      (node (ref "D20") (pin "1") (pinfunction "VDD_1") (pintype "power_in"))
      (node (ref "D21") (pin "1") (pinfunction "VDD_1") (pintype "power_in"))
      (node (ref "D22") (pin "1") (pinfunction "VDD_1") (pintype "power_in"))
      (node (ref "D23") (pin "1") (pinfunction "VDD_1") (pintype "power_in"))
      (node (ref "D24") (pin "1") (pinfunction "VDD_1") (pintype "power_in"))
      (node (ref "D25") (pin "1") (pinfunction "VDD_1") (pintype "power_in"))
      (node (ref "D3") (pin "1") (pinfunction "VDD_1") (pintype "power_in"))
      (node (ref "D4") (pin "1") (pinfunction "VDD_1") (pintype "power_in"))
      (node (ref "D5") (pin "1") (pinfunction "VDD_1") (pintype "power_in"))
      (node (ref "D6") (pin "1") (pinfunction "VDD_1") (pintype "power_in"))
      (node (ref "D7") (pin "1") (pinfunction "VDD_1") (pintype "power_in"))
      (node (ref "D8") (pin "1") (pinfunction "VDD_1") (pintype "power_in"))
      (node (ref "D9") (pin "1") (pinfunction "VDD_1") (pintype "power_in"))
      (node (ref "R27") (pin "2") (pinfunction "2_2") (pintype "passive"))
      (node (ref "SW1") (pin "1") (pinfunction "1_1") (pintype "passive"))
      (node (ref "U6") (pin "2") (pinfunction "VOUT_2") (pintype "bidirectional"))
      (node (ref "U6") (pin "3") (pinfunction "VOUT_3") (pintype "bidirectional"))
      (node (ref "U8") (pin "1") (pinfunction "IN_1") (pintype "input"))
      (node (ref "U8") (pin "3") (pinfunction "EN_3") (pintype "input"))
    )
    (net (code "70") (name "VDD_3.3") (class "Default")
      (node (ref "C20") (pin "A") (pinfunction "+_A") (pintype "passive"))
      (node (ref "C28") (pin "1") (pinfunction "1_1") (pintype "passive"))
      (node (ref "C29") (pin "1") (pinfunction "1_1") (pintype "passive"))
      (node (ref "R19") (pin "2") (pinfunction "2_2") (pintype "passive"))
      (node (ref "R28") (pin "2") (pinfunction "2_2") (pintype "passive"))
      (node (ref "U1") (pin "8") (pinfunction "VCC_8") (pintype "power_in"))
      (node (ref "U2") (pin "2") (pinfunction "VCC_2") (pintype "power_in"))
      (node (ref "U8") (pin "5") (pinfunction "OUT_5") (pintype "passive"))
    )
    (net (code "71") (name "VIN") (class "Default")
      (node (ref "C10") (pin "1") (pinfunction "1_1") (pintype "passive"))
      (node (ref "C11") (pin "1") (pinfunction "1_1") (pintype "passive"))
      (node (ref "C13") (pin "2") (pinfunction "2_2") (pintype "passive"))
      (node (ref "JP1") (pin "VBUS") (pinfunction "VBUS_VBUS") (pintype "bidirectional"))
      (node (ref "R5") (pin "2") (pinfunction "2_2") (pintype "passive"))
      (node (ref "R7") (pin "2") (pinfunction "2_2") (pintype "passive"))
      (node (ref "R8") (pin "2") (pinfunction "2_2") (pintype "passive"))
      (node (ref "S1") (pin "1") (pinfunction "O_1") (pintype "passive"))
      (node (ref "U3") (pin "4") (pinfunction "VCC_4") (pintype "bidirectional"))
      (node (ref "U4") (pin "7") (pinfunction "REGIN_7") (pintype "passive"))
      (node (ref "U4") (pin "8") (pinfunction "VBUS_8") (pintype "input"))
    )
    (net (code "72") (name "V_BATT") (class "Default")
      (node (ref "R11") (pin "1") (pinfunction "1_1") (pintype "passive"))
      (node (ref "R20") (pin "2") (pinfunction "2_2") (pintype "passive"))
      (node (ref "R27") (pin "1") (pinfunction "1_1") (pintype "passive"))
      (node (ref "S1") (pin "2") (pinfunction "P_2") (pintype "passive"))
      (node (ref "SW1") (pin "4") (pinfunction "4_4") (pintype "passive"))
      (node (ref "U5") (pin "1") (pinfunction "IN_1") (pintype "input"))
      (node (ref "U5") (pin "3") (pinfunction "EN_3") (pintype "input"))
      (node (ref "U6") (pin "4") (pinfunction "VIN_4") (pintype "bidirectional"))
    )
    (net (code "73") (name "WS2812") (class "Default")
      (node (ref "D1") (pin "4") (pinfunction "DIN_4") (pintype "input"))
      (node (ref "U7") (pin "18") (pinfunction "PA8_18") (pintype "bidirectional"))
    )
    (net (code "74") (name "unconnected-(D25-DOUT-Pad2)") (class "Default")
      (node (ref "D25") (pin "2") (pinfunction "DOUT_2") (pintype "output"))
    )
    (net (code "75") (name "unconnected-(JP1-MTN1-PadMTN3)") (class "Default")
      (node (ref "JP1") (pin "MTN3") (pinfunction "MTN1_MTN3") (pintype "bidirectional"))
    )
    (net (code "76") (name "unconnected-(JP1-MTN2-PadMTN1)") (class "Default")
      (node (ref "JP1") (pin "MTN1") (pinfunction "MTN2_MTN1") (pintype "bidirectional"))
    )
    (net (code "77") (name "unconnected-(JP1-MTN3-PadMTN2)") (class "Default")
      (node (ref "JP1") (pin "MTN2") (pinfunction "MTN3_MTN2") (pintype "bidirectional"))
    )
    (net (code "78") (name "unconnected-(JP1-PadID)") (class "Default")
      (node (ref "JP1") (pin "ID") (pinfunction "ID_ID") (pintype "bidirectional"))
    )
    (net (code "79") (name "unconnected-(JP1-PadMTN4)") (class "Default")
      (node (ref "JP1") (pin "MTN4") (pinfunction "MTN4_MTN4") (pintype "bidirectional"))
    )
    (net (code "80") (name "unconnected-(R26C-1-Pad4)") (class "Default")
      (node (ref "R26") (pin "4") (pinfunction "1_4") (pintype "passive"))
    )
    (net (code "81") (name "unconnected-(U2-32KHZ-Pad1)") (class "Default")
      (node (ref "U2") (pin "1") (pinfunction "32KHZ_1") (pintype "output"))
    )
    (net (code "82") (name "unconnected-(U4-CTS-Pad23)") (class "Default")
      (node (ref "U4") (pin "23") (pinfunction "CTS_23") (pintype "input"))
    )
    (net (code "83") (name "unconnected-(U4-DCD-Pad1)") (class "Default")
      (node (ref "U4") (pin "1") (pinfunction "DCD_1") (pintype "input"))
    )
    (net (code "84") (name "unconnected-(U4-DSR-Pad27)") (class "Default")
      (node (ref "U4") (pin "27") (pinfunction "DSR_27") (pintype "input"))
    )
    (net (code "85") (name "unconnected-(U4-DTR-Pad28)") (class "Default")
      (node (ref "U4") (pin "28") (pinfunction "DTR_28") (pintype "output"))
    )
    (net (code "86") (name "unconnected-(U4-RI-Pad2)") (class "Default")
      (node (ref "U4") (pin "2") (pinfunction "RI_2") (pintype "input"))
    )
    (net (code "87") (name "unconnected-(U4-RTS-Pad24)") (class "Default")
      (node (ref "U4") (pin "24") (pinfunction "RTS_24") (pintype "output"))
    )
    (net (code "88") (name "unconnected-(U4-SUSPEND-Pad12)") (class "Default")
      (node (ref "U4") (pin "12") (pinfunction "SUSPEND_12") (pintype "output"))
    )
    (net (code "89") (name "unconnected-(U7-PA2-Pad8)") (class "Default")
      (node (ref "U7") (pin "8") (pinfunction "PA2_8") (pintype "bidirectional"))
    )
    (net (code "90") (name "unconnected-(U7-PA3-Pad9)") (class "Default")
      (node (ref "U7") (pin "9") (pinfunction "PA3_9") (pintype "bidirectional"))
    )
    (net (code "91") (name "unconnected-(U7-PA12-Pad22)") (class "Default")
      (node (ref "U7") (pin "22") (pinfunction "PA12_22") (pintype "bidirectional"))
    )
    (net (code "92") (name "unconnected-(U7-PB3-Pad26)") (class "Default")
      (node (ref "U7") (pin "26") (pinfunction "PB3_26") (pintype "bidirectional"))
    )
    (net (code "93") (name "unconnected-(U7-PB4-Pad27)") (class "Default")
      (node (ref "U7") (pin "27") (pinfunction "PB4_27") (pintype "bidirectional"))
    )
    (net (code "94") (name "unconnected-(U7-PB5-Pad28)") (class "Default")
      (node (ref "U7") (pin "28") (pinfunction "PB5_28") (pintype "bidirectional"))
    )
    (net (code "95") (name "unconnected-(U9-NC-Pad3)") (class "Default")
      (node (ref "U9") (pin "3") (pinfunction "NC_3") (pintype "bidirectional"))
    )
    (net (code "96") (name "unconnected-(U9-NC-Pad10)") (class "Default")
      (node (ref "U9") (pin "10") (pinfunction "NC_10") (pintype "bidirectional"))
    )
    (net (code "97") (name "unconnected-(U9-NC-Pad11)") (class "Default")
      (node (ref "U9") (pin "11") (pinfunction "NC_11") (pintype "bidirectional"))
    )
  )
)
